# Op-Amp.net
KiCad netlist of a schematic drawn in Altium Designer
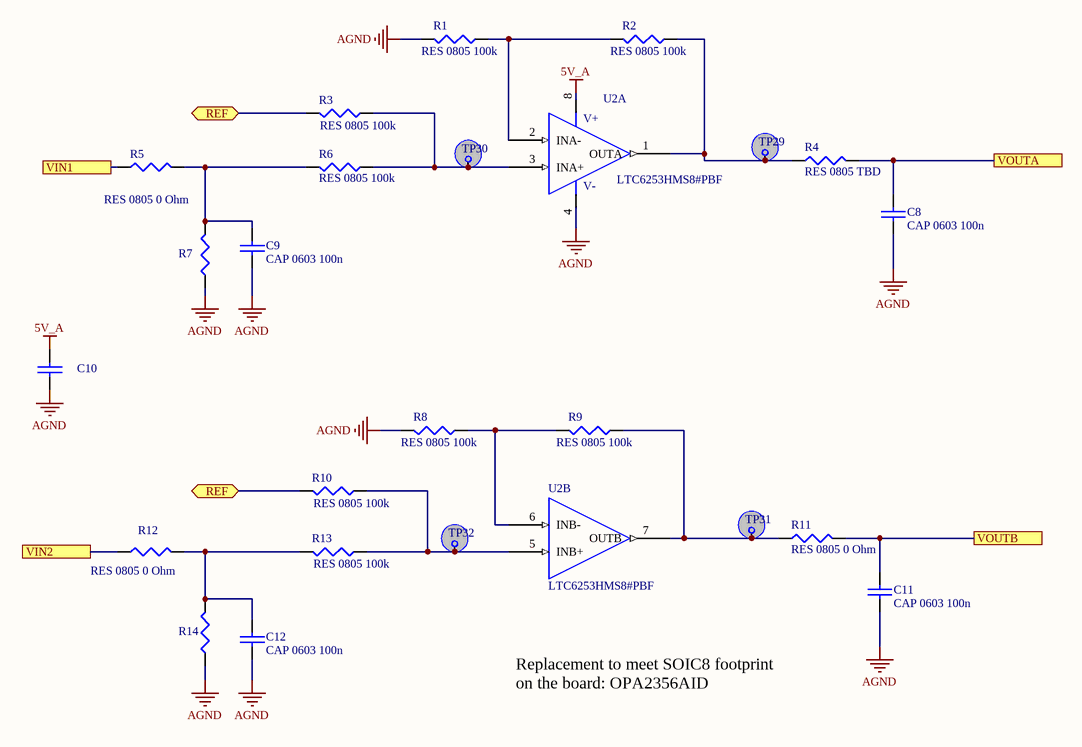
[diagram p0: Op-Amp.SchDoc]

(export (version "E")
  (design (tool "Eeschema 10.0.6"))
  (components
    (comp (ref "C8")
      (value "CAP 0603 100n")
      (footprint "CAPC1608N")
      (description "CAP 0603 TBD")
      (fields (field (name "PART#") "TBD"))
      (libsource (lib "SMD_R&C_V1.0") (part "CAP 0603 TBD"))
    )
    (comp (ref "C9")
      (value "CAP 0603 100n")
      (footprint "CAPC1608N")
      (description "CAP 0603 100 nF")
      (fields (field (name "PART#") "TBD"))
      (libsource (lib "SMD_R&C_V1.0") (part "CAP 0603 TBD"))
    )
    (comp (ref "C10")
      (value "CAP 0603 100nF 100V")
      (footprint "CAPC1608N")
      (description "CAP 0603 TBD")
      (fields (field (name "PART#") "TBD"))
      (libsource (lib "SMD_R&C_V1.0") (part "CAP 0603 TBD"))
    )
    (comp (ref "C11")
      (value "CAP 0603 100n")
      (footprint "CAPC1608N")
      (description "CAP 0603 TBD")
      (fields (field (name "PART#") "TBD"))
      (libsource (lib "SMD_R&C_V1.0") (part "CAP 0603 TBD"))
    )
    (comp (ref "C12")
      (value "CAP 0603 100n")
      (footprint "CAPC1608N")
      (description "CAP 0603 TBD")
      (fields (field (name "PART#") "TBD"))
      (libsource (lib "SMD_R&C_V1.0") (part "CAP 0603 TBD"))
    )
    (comp (ref "R1")
      (value "RES 0805 100k")
      (footprint "RES2012N")
      (description "RES 0805 TBD")
      (fields (field (name "PART#") "TBD"))
      (libsource (lib "SMD_R&C_V1.0") (part "RES 0805 TBD"))
    )
    (comp (ref "R2")
      (value "RES 0805 100k")
      (footprint "RES2012N")
      (description "RES 0805 TBD")
      (fields (field (name "PART#") "TBD"))
      (libsource (lib "SMD_R&C_V1.0") (part "RES 0805 TBD"))
    )
    (comp (ref "R3")
      (value "RES 0805 100k")
      (footprint "RES2012N")
      (description "RES 0805 TBD")
      (fields (field (name "PART#") "TBD"))
      (libsource (lib "SMD_R&C_V1.0") (part "RES 0805 TBD"))
    )
    (comp (ref "R4")
      (value "RES 0805 TBD")
      (footprint "RES2012N")
      (fields (field (name "PART#") "TBD"))
      (libsource (lib "SMD_R&C_V1.0") (part "RES 0805 TBD"))
    )
    (comp (ref "R5")
      (value "RES 0805 0 Ohm")
      (footprint "RES2012N")
      (description "RES 0805 TBD")
      (fields (field (name "PART#") "TBD"))
      (libsource (lib "SMD_R&C_V1.0") (part "RES 0805 TBD"))
    )
    (comp (ref "R6")
      (value "RES 0805 100k")
      (footprint "RES2012N")
      (description "RES 0805 TBD")
      (fields (field (name "PART#") "TBD"))
      (libsource (lib "SMD_R&C_V1.0") (part "RES 0805 TBD"))
    )
    (comp (ref "R7")
      (value "RES 0805 10k")
      (footprint "RES2012N")
      (description "RES 0805 TBD")
      (fields (field (name "PART#") "TBD"))
      (libsource (lib "SMD_R&C_V1.0") (part "RES 0805 TBD"))
    )
    (comp (ref "R8")
      (value "RES 0805 100k")
      (footprint "RES2012N")
      (description "RES 0805 TBD")
      (fields (field (name "PART#") "TBD"))
      (libsource (lib "SMD_R&C_V1.0") (part "RES 0805 TBD"))
    )
    (comp (ref "R9")
      (value "RES 0805 100k")
      (footprint "RES2012N")
      (description "RES 0805 TBD")
      (fields (field (name "PART#") "TBD"))
      (libsource (lib "SMD_R&C_V1.0") (part "RES 0805 TBD"))
    )
    (comp (ref "R10")
      (value "RES 0805 100k")
      (footprint "RES2012N")
      (description "RES 0805 TBD")
      (fields (field (name "PART#") "TBD"))
      (libsource (lib "SMD_R&C_V1.0") (part "RES 0805 TBD"))
    )
    (comp (ref "R11")
      (value "RES 0805 0 Ohm")
      (footprint "RES2012N")
      (description "RES 0805 TBD")
      (fields (field (name "PART#") "TBD"))
      (libsource (lib "SMD_R&C_V1.0") (part "RES 0805 TBD"))
    )
    (comp (ref "R12")
      (value "RES 0805 0 Ohm")
      (footprint "RES2012N")
      (description "RES 0805 TBD")
      (fields (field (name "PART#") "TBD"))
      (libsource (lib "SMD_R&C_V1.0") (part "RES 0805 TBD"))
    )
    (comp (ref "R13")
      (value "RES 0805 100k")
      (footprint "RES2012N")
      (description "RES 0805 TBD")
      (fields (field (name "PART#") "TBD"))
      (libsource (lib "SMD_R&C_V1.0") (part "RES 0805 TBD"))
    )
    (comp (ref "R14")
      (value "RES 0805 10k")
      (footprint "RES2012N")
      (description "RES 0805 TBD")
      (fields (field (name "PART#") "TBD"))
      (libsource (lib "SMD_R&C_V1.0") (part "RES 0805 TBD"))
    )
    (comp (ref "TP29")
      (value "*")
      (footprint "Keystone 5000")
      (libsource (lib "Aarons_Library") (part "TEST_POINT_HOOK"))
    )
    (comp (ref "TP30")
      (value "*")
      (footprint "Keystone 5000")
      (libsource (lib "Aarons_Library") (part "TEST_POINT_HOOK"))
    )
    (comp (ref "TP31")
      (value "*")
      (footprint "Keystone 5000")
      (libsource (lib "Aarons_Library") (part "TEST_POINT_HOOK"))
    )
    (comp (ref "TP32")
      (value "*")
      (footprint "Keystone 5000")
      (libsource (lib "Aarons_Library") (part "TEST_POINT_HOOK"))
    )
    (comp (ref "U2")
      (value "LTC6253HMS8#PBF")
      (footprint "SOIC-8")
      (description "720MHz, 3.5mA Power\r\nEfficient Rail-to-Rail\r\nI/O Op Amps")
      (fields
        (field (name "MANUFACTURER") "Texas Instruments")
        (field (name "GENERIC_PART_NUMBER") "OPA2140")
      )
      (libsource (lib "Analog_Op-amp") (part "LTC6253HMS8#PBF"))
    )
  )
  (nets
    (net (code "1") (name "/REF") (class "Default")
      (node (ref "R10") (pin "2") (pinfunction "2_2") (pintype "passive"))
      (node (ref "R3") (pin "2") (pinfunction "2_2") (pintype "passive"))
    )
    (net (code "2") (name "/VIN1") (class "Default")
      (node (ref "R5") (pin "1") (pinfunction "1_1") (pintype "passive"))
    )
    (net (code "3") (name "/VIN2") (class "Default")
      (node (ref "R12") (pin "1") (pinfunction "1_1") (pintype "passive"))
    )
    (net (code "4") (name "/VOUTA") (class "Default")
      (node (ref "C8") (pin "1") (pintype "passive"))
      (node (ref "R4") (pin "2") (pinfunction "2_2") (pintype "passive"))
    )
    (net (code "5") (name "/VOUTB") (class "Default")
      (node (ref "C11") (pin "1") (pintype "passive"))
      (node (ref "R11") (pin "2") (pinfunction "2_2") (pintype "passive"))
    )
    (net (code "6") (name "5V_A") (class "Default")
      (node (ref "C10") (pin "2") (pintype "passive"))
      (node (ref "U2") (pin "8") (pinfunction "V+_8") (pintype "power_in"))
    )
    (net (code "7") (name "AGND") (class "Default")
      (node (ref "C10") (pin "1") (pintype "passive"))
      (node (ref "C11") (pin "2") (pintype "passive"))
      (node (ref "C12") (pin "2") (pintype "passive"))
      (node (ref "C8") (pin "2") (pintype "passive"))
      (node (ref "C9") (pin "2") (pintype "passive"))
      (node (ref "R1") (pin "2") (pinfunction "2_2") (pintype "passive"))
      (node (ref "R14") (pin "1") (pinfunction "1_1") (pintype "passive"))
      (node (ref "R7") (pin "1") (pinfunction "1_1") (pintype "passive"))
      (node (ref "R8") (pin "2") (pinfunction "2_2") (pintype "passive"))
      (node (ref "U2") (pin "4") (pinfunction "V-_4") (pintype "power_in"))
    )
    (net (code "8") (name "Net-(C9-Pad1)") (class "Default")
      (node (ref "C9") (pin "1") (pintype "passive"))
      (node (ref "R5") (pin "2") (pinfunction "2_2") (pintype "passive"))
      (node (ref "R6") (pin "2") (pinfunction "2_2") (pintype "passive"))
      (node (ref "R7") (pin "2") (pinfunction "2_2") (pintype "passive"))
    )
    (net (code "9") (name "Net-(C12-Pad1)") (class "Default")
      (node (ref "C12") (pin "1") (pintype "passive"))
      (node (ref "R12") (pin "2") (pinfunction "2_2") (pintype "passive"))
      (node (ref "R13") (pin "2") (pinfunction "2_2") (pintype "passive"))
      (node (ref "R14") (pin "2") (pinfunction "2_2") (pintype "passive"))
    )
    (net (code "10") (name "Net-(U2A-INA+)") (class "Default")
      (node (ref "R3") (pin "1") (pinfunction "1_1") (pintype "passive"))
      (node (ref "R6") (pin "1") (pinfunction "1_1") (pintype "passive"))
      (node (ref "TP30") (pin "1") (pinfunction "1_1") (pintype "passive"))
      (node (ref "U2") (pin "3") (pinfunction "INA+_3") (pintype "input"))
    )
    (net (code "11") (name "Net-(U2A-INA-)") (class "Default")
      (node (ref "R1") (pin "1") (pinfunction "1_1") (pintype "passive"))
      (node (ref "R2") (pin "2") (pinfunction "2_2") (pintype "passive"))
      (node (ref "U2") (pin "2") (pinfunction "INA-_2") (pintype "input"))
    )
    (net (code "12") (name "Net-(U2A-OUTA)") (class "Default")
      (node (ref "R2") (pin "1") (pinfunction "1_1") (pintype "passive"))
      (node (ref "R4") (pin "1") (pinfunction "1_1") (pintype "passive"))
      (node (ref "TP29") (pin "1") (pinfunction "1_1") (pintype "passive"))
      (node (ref "U2") (pin "1") (pinfunction "OUTA_1") (pintype "output"))
    )
    (net (code "13") (name "Net-(U2B-INB+)") (class "Default")
      (node (ref "R10") (pin "1") (pinfunction "1_1") (pintype "passive"))
      (node (ref "R13") (pin "1") (pinfunction "1_1") (pintype "passive"))
      (node (ref "TP32") (pin "1") (pinfunction "1_1") (pintype "passive"))
      (node (ref "U2") (pin "5") (pinfunction "INB+_5") (pintype "input"))
    )
    (net (code "14") (name "Net-(U2B-INB-)") (class "Default")
      (node (ref "R8") (pin "1") (pinfunction "1_1") (pintype "passive"))
      (node (ref "R9") (pin "2") (pinfunction "2_2") (pintype "passive"))
      (node (ref "U2") (pin "6") (pinfunction "INB-_6") (pintype "input"))
    )
    (net (code "15") (name "Net-(U2B-OUTB)") (class "Default")
      (node (ref "R11") (pin "1") (pinfunction "1_1") (pintype "passive"))
      (node (ref "R9") (pin "1") (pinfunction "1_1") (pintype "passive"))
      (node (ref "TP31") (pin "1") (pinfunction "1_1") (pintype "passive"))
      (node (ref "U2") (pin "7") (pinfunction "OUTB_7") (pintype "output"))
    )
  )
)
